# frankShield-v2.net
KiCad netlist of a schematic drawn in EAGLE
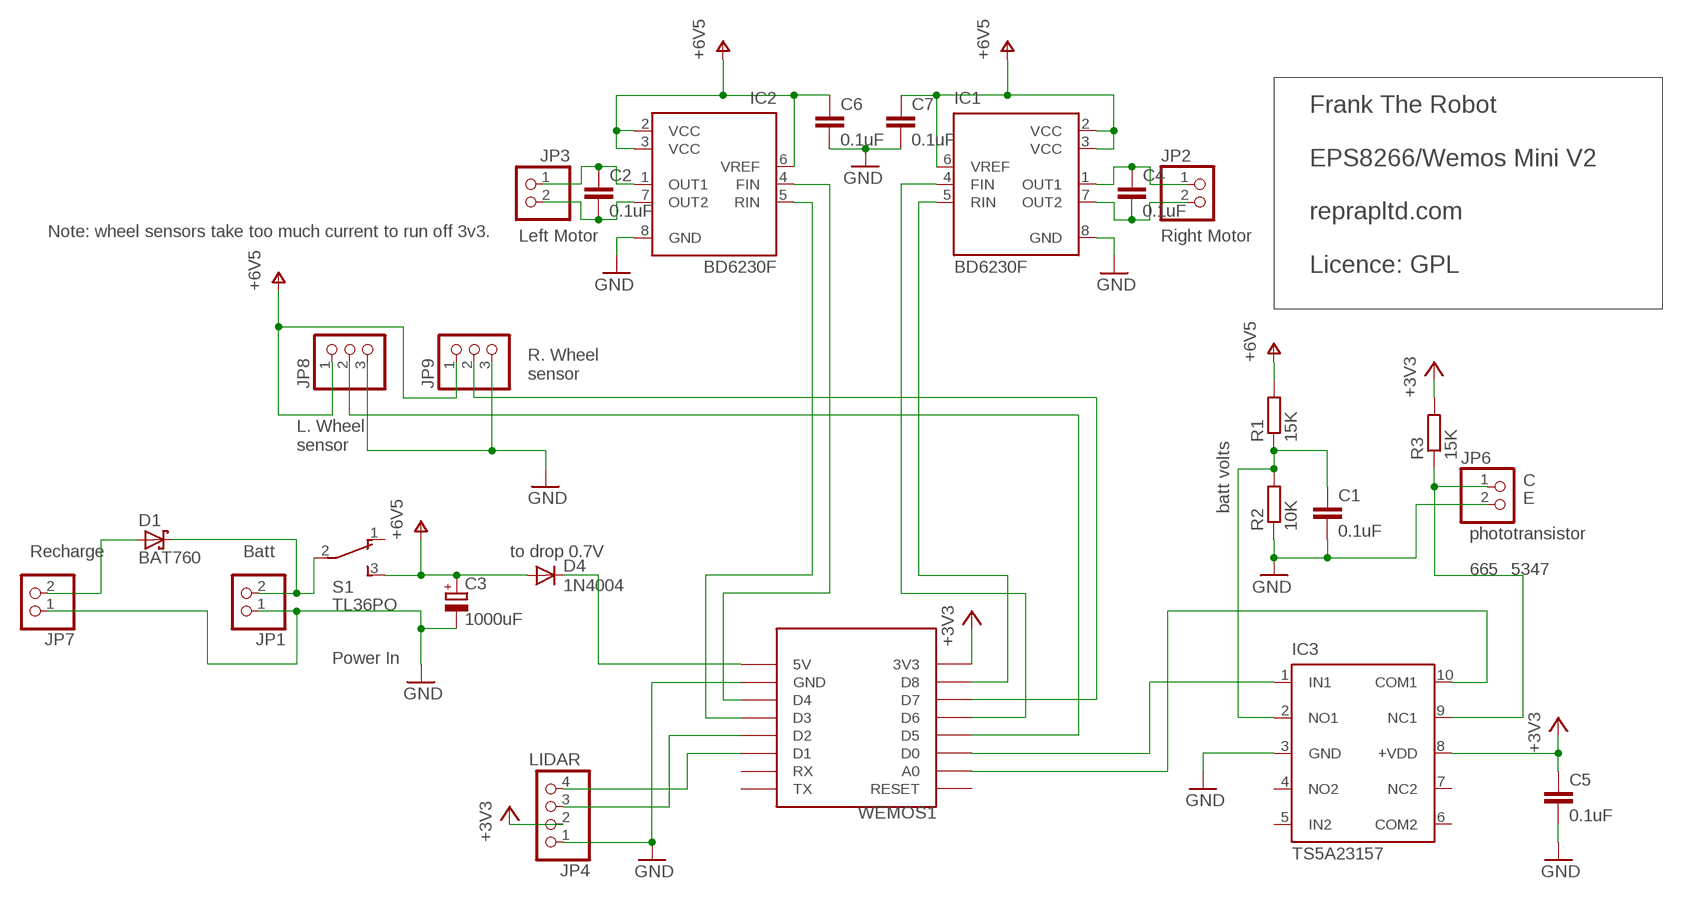
[diagram p0: schematic, sheet 1]

(export (version "E")
  (design (tool "Eeschema 10.0.6"))
  (components
    (comp (ref "C1")
      (value "0.1uF")
      (footprint "eagle-import:C0805")
      (libsource (lib "eagle-import") (part "C-EUC0805"))
    )
    (comp (ref "C2")
      (value "0.1uF")
      (footprint "eagle-import:C0805")
      (libsource (lib "eagle-import") (part "C-EUC0805"))
    )
    (comp (ref "C3")
      (value "1000uF")
      (footprint "eagle-import:B45181B")
      (libsource (lib "eagle-import") (part "CPOL-EUB45181B"))
    )
    (comp (ref "C4")
      (value "0.1uF")
      (footprint "eagle-import:C0805")
      (libsource (lib "eagle-import") (part "C-EUC0805"))
    )
    (comp (ref "C5")
      (value "0.1uF")
      (footprint "eagle-import:C0805")
      (libsource (lib "eagle-import") (part "C-EUC0805"))
    )
    (comp (ref "C6")
      (value "0.1uF")
      (footprint "eagle-import:C0805")
      (libsource (lib "eagle-import") (part "C-EUC0805"))
    )
    (comp (ref "C7")
      (value "0.1uF")
      (footprint "eagle-import:C0805")
      (libsource (lib "eagle-import") (part "C-EUC0805"))
    )
    (comp (ref "D1")
      (value "BAT760")
      (footprint "eagle-import:SOD323_ST")
      (libsource (lib "eagle-import") (part "BAT60J"))
    )
    (comp (ref "D4")
      (value "1N4004")
      (footprint "eagle-import:DO41-10")
      (libsource (lib "eagle-import") (part "1N4004"))
    )
    (comp (ref "IC1")
      (value "BD6230F")
      (footprint "eagle-import:SOP8")
      (fields (field (name "MPN") "BD6230F-E2"))
      (libsource (lib "eagle-import") (part "BD623F0"))
    )
    (comp (ref "IC2")
      (value "BD6230F")
      (footprint "eagle-import:SOP8")
      (fields (field (name "MPN") "BD6230F-E2"))
      (libsource (lib "eagle-import") (part "BD623F0"))
    )
    (comp (ref "IC3")
      (value "TS5A23157")
      (footprint "eagle-import:MSOP10")
      (fields (field (name "MPN") "AD7992BRMZ-0"))
      (libsource (lib "eagle-import") (part "TS5A23157"))
    )
    (comp (ref "JP1")
      (value "PINHD-1X2")
      (footprint "eagle-import:1X02")
      (libsource (lib "eagle-import") (part "PINHD-1X2"))
    )
    (comp (ref "JP2")
      (value "PINHD-1X2")
      (footprint "eagle-import:1X02")
      (libsource (lib "eagle-import") (part "PINHD-1X2"))
    )
    (comp (ref "JP3")
      (value "PINHD-1X2")
      (footprint "eagle-import:1X02")
      (libsource (lib "eagle-import") (part "PINHD-1X2"))
    )
    (comp (ref "JP4")
      (value "PINHD-1X4")
      (footprint "eagle-import:1X04")
      (libsource (lib "eagle-import") (part "PINHD-1X4"))
    )
    (comp (ref "JP6")
      (value "PINHD-1X2")
      (footprint "eagle-import:1X02")
      (libsource (lib "eagle-import") (part "PINHD-1X2"))
    )
    (comp (ref "JP7")
      (value "PINHD-1X2")
      (footprint "eagle-import:1X02")
      (libsource (lib "eagle-import") (part "PINHD-1X2"))
    )
    (comp (ref "JP8")
      (value "PINHD-1X3")
      (footprint "eagle-import:1X03")
      (libsource (lib "eagle-import") (part "PINHD-1X3"))
    )
    (comp (ref "JP9")
      (value "PINHD-1X3")
      (footprint "eagle-import:1X03")
      (libsource (lib "eagle-import") (part "PINHD-1X3"))
    )
    (comp (ref "R1")
      (value "15K")
      (footprint "eagle-import:M0805")
      (libsource (lib "eagle-import") (part "R-EU_M0805"))
    )
    (comp (ref "R2")
      (value "10K")
      (footprint "eagle-import:M0805")
      (libsource (lib "eagle-import") (part "R-EU_M0805"))
    )
    (comp (ref "R3")
      (value "15K")
      (footprint "eagle-import:M0805")
      (libsource (lib "eagle-import") (part "R-EU_M0805"))
    )
    (comp (ref "S1")
      (value "TL36PO")
      (footprint "eagle-import:TL3XPO")
      (libsource (lib "eagle-import") (part "TL36PO"))
    )
    (comp (ref "WEMOS1")
      (value "WEMOS-D1-MINI")
      (footprint "eagle-import:WEMOS-D1-MINI")
      (libsource (lib "eagle-import") (part "WEMOS-D1-MINI"))
    )
  )
  (nets
    (net (code "1") (name "+3V3") (class "Default")
      (node (ref "C5") (pin "1") (pinfunction "1_1") (pintype "passive"))
      (node (ref "IC3") (pin "8") (pinfunction "+VDD_8") (pintype "output"))
      (node (ref "JP4") (pin "2") (pinfunction "2_2") (pintype "passive"))
      (node (ref "R3") (pin "2") (pinfunction "2_2") (pintype "passive"))
      (node (ref "WEMOS1") (pin "3V3") (pinfunction "3V3_3V3") (pintype "bidirectional"))
    )
    (net (code "2") (name "+6V5") (class "Default")
      (node (ref "C3") (pin "+") (pinfunction "+_+") (pintype "passive"))
      (node (ref "C6") (pin "1") (pinfunction "1_1") (pintype "passive"))
      (node (ref "C7") (pin "1") (pinfunction "1_1") (pintype "passive"))
      (node (ref "D4") (pin "A") (pinfunction "A_A") (pintype "passive"))
      (node (ref "IC1") (pin "2") (pinfunction "VCC_2") (pintype "power_in"))
      (node (ref "IC1") (pin "3") (pinfunction "VCC_3") (pintype "power_in"))
      (node (ref "IC1") (pin "6") (pinfunction "VREF_6") (pintype "passive"))
      (node (ref "IC2") (pin "2") (pinfunction "VCC_2") (pintype "power_in"))
      (node (ref "IC2") (pin "3") (pinfunction "VCC_3") (pintype "power_in"))
      (node (ref "IC2") (pin "6") (pinfunction "VREF_6") (pintype "passive"))
      (node (ref "JP8") (pin "1") (pinfunction "1_1") (pintype "passive"))
      (node (ref "JP9") (pin "1") (pinfunction "1_1") (pintype "passive"))
      (node (ref "R1") (pin "2") (pinfunction "2_2") (pintype "passive"))
      (node (ref "S1") (pin "3") (pinfunction "S_3") (pintype "passive"))
    )
    (net (code "3") (name "/NC2") (class "Default")
      (node (ref "IC3") (pin "7") (pinfunction "NC2_7") (pintype "power_in"))
    )
    (net (code "4") (name "GND") (class "Default")
      (node (ref "C1") (pin "2") (pinfunction "2_2") (pintype "passive"))
      (node (ref "C3") (pin "-") (pinfunction "-_-") (pintype "passive"))
      (node (ref "C5") (pin "2") (pinfunction "2_2") (pintype "passive"))
      (node (ref "C6") (pin "2") (pinfunction "2_2") (pintype "passive"))
      (node (ref "C7") (pin "2") (pinfunction "2_2") (pintype "passive"))
      (node (ref "IC1") (pin "8") (pinfunction "GND_8") (pintype "power_in"))
      (node (ref "IC2") (pin "8") (pinfunction "GND_8") (pintype "power_in"))
      (node (ref "IC3") (pin "3") (pinfunction "GND_3") (pintype "power_in"))
      (node (ref "JP1") (pin "1") (pinfunction "1_1") (pintype "passive"))
      (node (ref "JP4") (pin "1") (pinfunction "1_1") (pintype "passive"))
      (node (ref "JP6") (pin "2") (pinfunction "2_2") (pintype "passive"))
      (node (ref "JP7") (pin "1") (pinfunction "1_1") (pintype "passive"))
      (node (ref "JP8") (pin "3") (pinfunction "3_3") (pintype "passive"))
      (node (ref "JP9") (pin "3") (pinfunction "3_3") (pintype "passive"))
      (node (ref "R2") (pin "1") (pinfunction "1_1") (pintype "passive"))
      (node (ref "WEMOS1") (pin "GND") (pinfunction "GND_GND") (pintype "bidirectional"))
    )
    (net (code "5") (name "Net-(D1-PadA)") (class "Default")
      (node (ref "D1") (pin "A") (pinfunction "A_A") (pintype "passive"))
      (node (ref "JP7") (pin "2") (pinfunction "2_2") (pintype "passive"))
    )
    (net (code "6") (name "Net-(D4-PadC)") (class "Default")
      (node (ref "D4") (pin "C") (pinfunction "C_C") (pintype "passive"))
      (node (ref "WEMOS1") (pin "5V") (pinfunction "5V_5V") (pintype "bidirectional"))
    )
    (net (code "7") (name "Net-(IC1-FIN)") (class "Default")
      (node (ref "IC1") (pin "4") (pinfunction "FIN_4") (pintype "input"))
      (node (ref "WEMOS1") (pin "D6") (pinfunction "D6_D6") (pintype "bidirectional"))
    )
    (net (code "8") (name "Net-(IC1-OUT1)") (class "Default")
      (node (ref "C4") (pin "1") (pinfunction "1_1") (pintype "passive"))
      (node (ref "IC1") (pin "1") (pinfunction "OUT1_1") (pintype "output"))
      (node (ref "JP2") (pin "1") (pinfunction "1_1") (pintype "passive"))
    )
    (net (code "9") (name "Net-(IC1-OUT2)") (class "Default")
      (node (ref "C4") (pin "2") (pinfunction "2_2") (pintype "passive"))
      (node (ref "IC1") (pin "7") (pinfunction "OUT2_7") (pintype "output"))
      (node (ref "JP2") (pin "2") (pinfunction "2_2") (pintype "passive"))
    )
    (net (code "10") (name "Net-(IC1-RIN)") (class "Default")
      (node (ref "IC1") (pin "5") (pinfunction "RIN_5") (pintype "input"))
      (node (ref "WEMOS1") (pin "D8") (pinfunction "D8_D8") (pintype "bidirectional"))
    )
    (net (code "11") (name "Net-(IC2-FIN)") (class "Default")
      (node (ref "IC2") (pin "4") (pinfunction "FIN_4") (pintype "input"))
      (node (ref "WEMOS1") (pin "D4") (pinfunction "D4_D4") (pintype "bidirectional"))
    )
    (net (code "12") (name "Net-(IC2-OUT1)") (class "Default")
      (node (ref "C2") (pin "1") (pinfunction "1_1") (pintype "passive"))
      (node (ref "IC2") (pin "1") (pinfunction "OUT1_1") (pintype "output"))
      (node (ref "JP3") (pin "1") (pinfunction "1_1") (pintype "passive"))
    )
    (net (code "13") (name "Net-(IC2-OUT2)") (class "Default")
      (node (ref "C2") (pin "2") (pinfunction "2_2") (pintype "passive"))
      (node (ref "IC2") (pin "7") (pinfunction "OUT2_7") (pintype "output"))
      (node (ref "JP3") (pin "2") (pinfunction "2_2") (pintype "passive"))
    )
    (net (code "14") (name "Net-(IC2-RIN)") (class "Default")
      (node (ref "IC2") (pin "5") (pinfunction "RIN_5") (pintype "input"))
      (node (ref "WEMOS1") (pin "D3") (pinfunction "D3_D3") (pintype "bidirectional"))
    )
    (net (code "15") (name "Net-(IC3-COM1)") (class "Default")
      (node (ref "IC3") (pin "10") (pinfunction "COM1_10") (pintype "input"))
      (node (ref "WEMOS1") (pin "A0") (pinfunction "A0_A0") (pintype "bidirectional"))
    )
    (net (code "16") (name "Net-(IC3-IN1)") (class "Default")
      (node (ref "IC3") (pin "1") (pinfunction "IN1_1") (pintype "input"))
      (node (ref "WEMOS1") (pin "D0") (pinfunction "D0_D0") (pintype "bidirectional"))
    )
    (net (code "17") (name "Net-(IC3-NC1)") (class "Default")
      (node (ref "IC3") (pin "9") (pinfunction "NC1_9") (pintype "bidirectional"))
      (node (ref "JP6") (pin "1") (pinfunction "1_1") (pintype "passive"))
      (node (ref "R3") (pin "1") (pinfunction "1_1") (pintype "passive"))
    )
    (net (code "18") (name "Net-(IC3-NO1)") (class "Default")
      (node (ref "C1") (pin "1") (pinfunction "1_1") (pintype "passive"))
      (node (ref "IC3") (pin "2") (pinfunction "NO1_2") (pintype "power_in"))
      (node (ref "R1") (pin "1") (pinfunction "1_1") (pintype "passive"))
      (node (ref "R2") (pin "2") (pinfunction "2_2") (pintype "passive"))
    )
    (net (code "19") (name "Net-(JP4-Pad3)") (class "Default")
      (node (ref "JP4") (pin "3") (pinfunction "3_3") (pintype "passive"))
      (node (ref "WEMOS1") (pin "D2") (pinfunction "D2_D2") (pintype "bidirectional"))
    )
    (net (code "20") (name "Net-(JP4-Pad4)") (class "Default")
      (node (ref "JP4") (pin "4") (pinfunction "4_4") (pintype "passive"))
      (node (ref "WEMOS1") (pin "D1") (pinfunction "D1_D1") (pintype "bidirectional"))
    )
    (net (code "21") (name "Net-(JP8-Pad2)") (class "Default")
      (node (ref "JP8") (pin "2") (pinfunction "2_2") (pintype "passive"))
      (node (ref "WEMOS1") (pin "D5") (pinfunction "D5_D5") (pintype "bidirectional"))
    )
    (net (code "22") (name "Net-(JP9-Pad2)") (class "Default")
      (node (ref "JP9") (pin "2") (pinfunction "2_2") (pintype "passive"))
      (node (ref "WEMOS1") (pin "D7") (pinfunction "D7_D7") (pintype "bidirectional"))
    )
    (net (code "23") (name "Net-(S1-P)") (class "Default")
      (node (ref "D1") (pin "C") (pinfunction "C_C") (pintype "passive"))
      (node (ref "JP1") (pin "2") (pinfunction "2_2") (pintype "passive"))
      (node (ref "S1") (pin "2") (pinfunction "P_2") (pintype "passive"))
    )
    (net (code "24") (name "unconnected-(IC3-COM2-Pad6)") (class "Default")
      (node (ref "IC3") (pin "6") (pinfunction "COM2_6") (pintype "input"))
    )
    (net (code "25") (name "unconnected-(IC3-IN2-Pad5)") (class "Default")
      (node (ref "IC3") (pin "5") (pinfunction "IN2_5") (pintype "input"))
    )
    (net (code "26") (name "unconnected-(IC3-NO2-Pad4)") (class "Default")
      (node (ref "IC3") (pin "4") (pinfunction "NO2_4") (pintype "input"))
    )
    (net (code "27") (name "unconnected-(S1-O-Pad1)") (class "Default")
      (node (ref "S1") (pin "1") (pinfunction "O_1") (pintype "passive"))
    )
    (net (code "28") (name "unconnected-(WEMOS1-PadRESET)") (class "Default")
      (node (ref "WEMOS1") (pin "RESET") (pinfunction "RESET_RESET") (pintype "bidirectional"))
    )
    (net (code "29") (name "unconnected-(WEMOS1-PadRX)") (class "Default")
      (node (ref "WEMOS1") (pin "RX") (pinfunction "RX_RX") (pintype "bidirectional"))
    )
    (net (code "30") (name "unconnected-(WEMOS1-PadTX)") (class "Default")
      (node (ref "WEMOS1") (pin "TX") (pinfunction "TX_TX") (pintype "bidirectional"))
    )
  )
)
